# cytron-1.net
KiCad netlist of a schematic drawn in EAGLE
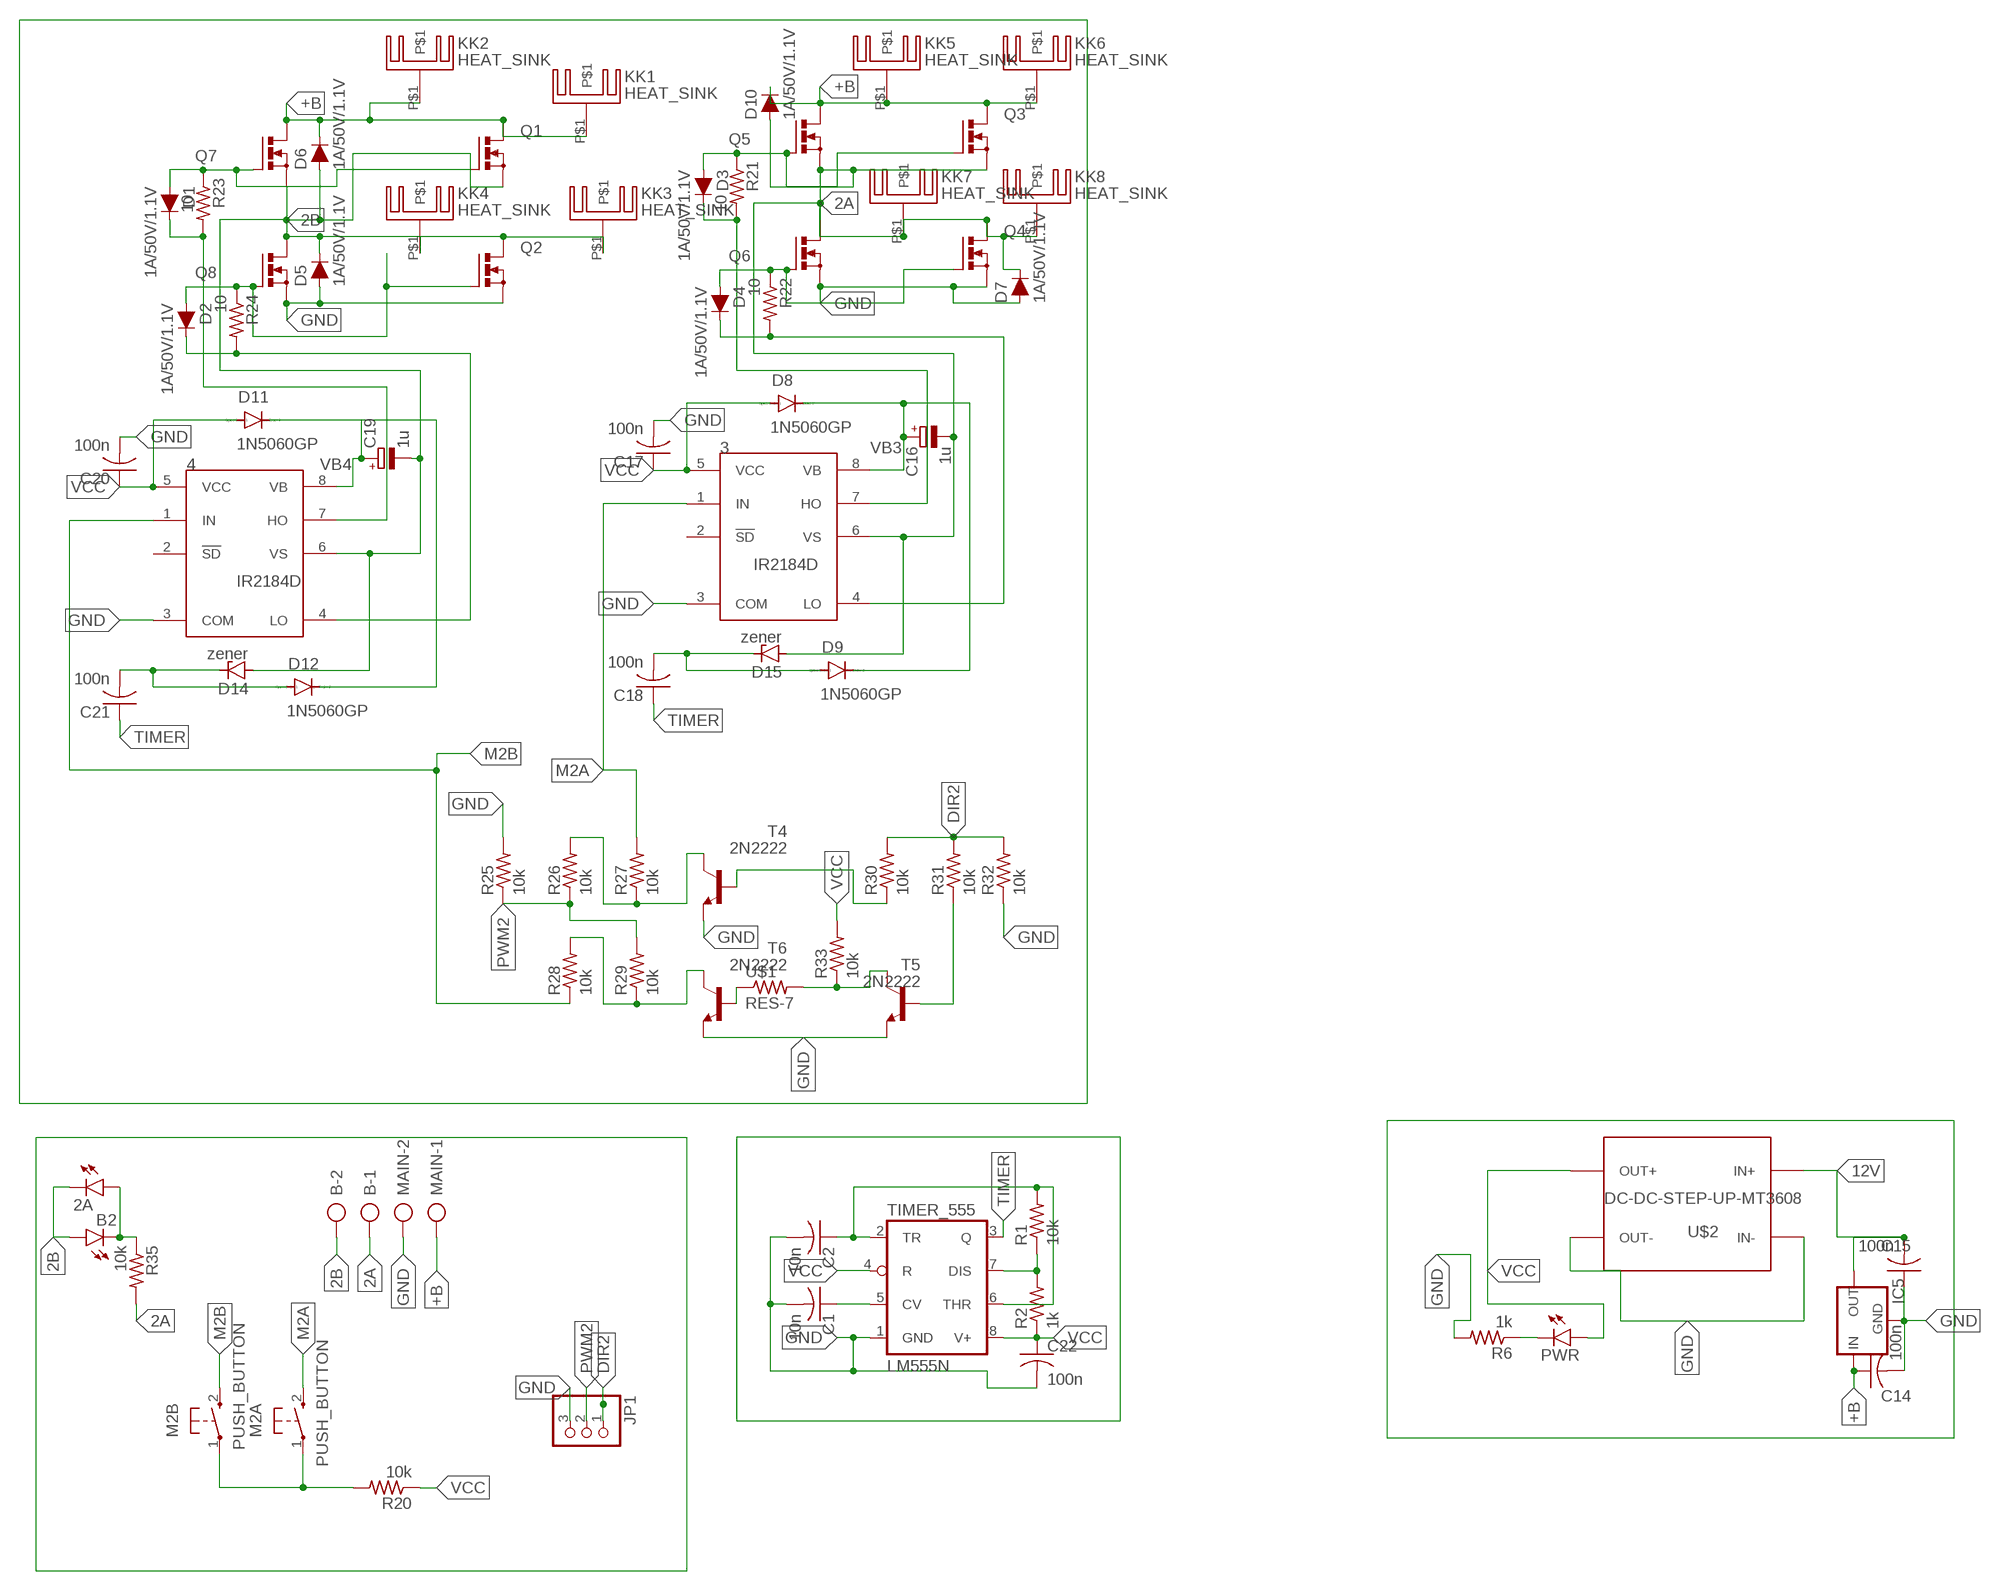
[diagram p0: schematic, sheet 1]

(export (version "E")
  (design (tool "Eeschema 10.0.6"))
  (components
    (comp (ref "2A")
      (value "LED3MM")
      (footprint "eagle-import:LED3MM")
      (libsource (lib "eagle-import") (part "LED3MM"))
    )
    (comp (ref "3")
      (value "IR2184D")
      (footprint "eagle-import:DIL08")
      (libsource (lib "eagle-import") (part "IR2184D"))
    )
    (comp (ref "4")
      (value "IR2184D")
      (footprint "eagle-import:DIL08")
      (libsource (lib "eagle-import") (part "IR2184D"))
    )
    (comp (ref "B")
      (value "ROSTA.POWER")
      (footprint "eagle-import:W239-302")
      (libsource (lib "eagle-import") (part "ROSTA.POWER"))
    )
    (comp (ref "B2")
      (value "LED3MM")
      (footprint "eagle-import:LED3MM")
      (libsource (lib "eagle-import") (part "LED3MM"))
    )
    (comp (ref "C1")
      (value "10n")
      (footprint "eagle-import:C025-025X050")
      (libsource (lib "eagle-import") (part "C-US025-025X050"))
    )
    (comp (ref "C2")
      (value "10n")
      (footprint "eagle-import:C025-025X050")
      (libsource (lib "eagle-import") (part "C-US025-025X050"))
    )
    (comp (ref "C14")
      (value "100n")
      (footprint "eagle-import:C025-025X050")
      (libsource (lib "eagle-import") (part "C-US025-025X050"))
    )
    (comp (ref "C15")
      (value "100n")
      (footprint "eagle-import:C025-025X050")
      (libsource (lib "eagle-import") (part "C-US025-025X050"))
    )
    (comp (ref "C16")
      (value "1u")
      (footprint "eagle-import:E5-5")
      (libsource (lib "eagle-import") (part "CPOL-EUE5-5"))
    )
    (comp (ref "C17")
      (value "100n")
      (footprint "eagle-import:C025-025X050")
      (libsource (lib "eagle-import") (part "C-US025-025X050"))
    )
    (comp (ref "C18")
      (value "100n")
      (footprint "eagle-import:C025-025X050")
      (libsource (lib "eagle-import") (part "C-US025-025X050"))
    )
    (comp (ref "C19")
      (value "1u")
      (footprint "eagle-import:E5-5")
      (libsource (lib "eagle-import") (part "CPOL-EUE5-5"))
    )
    (comp (ref "C20")
      (value "100n")
      (footprint "eagle-import:C025-025X050")
      (libsource (lib "eagle-import") (part "C-US025-025X050"))
    )
    (comp (ref "C21")
      (value "100n")
      (footprint "eagle-import:C025-025X050")
      (libsource (lib "eagle-import") (part "C-US025-025X050"))
    )
    (comp (ref "C22")
      (value "100n")
      (footprint "eagle-import:C025-025X050")
      (libsource (lib "eagle-import") (part "C-US025-025X050"))
    )
    (comp (ref "D1")
      (value "1A/50V/1.1V")
      (footprint "eagle-import:DIODE-1N4001")
      (libsource (lib "eagle-import") (part "DIODE(1A)-PTH"))
    )
    (comp (ref "D2")
      (value "1A/50V/1.1V")
      (footprint "eagle-import:DIODE-1N4001")
      (libsource (lib "eagle-import") (part "DIODE(1A)-PTH"))
    )
    (comp (ref "D3")
      (value "1A/50V/1.1V")
      (footprint "eagle-import:DIODE-1N4001")
      (libsource (lib "eagle-import") (part "DIODE(1A)-PTH"))
    )
    (comp (ref "D4")
      (value "1A/50V/1.1V")
      (footprint "eagle-import:DIODE-1N4001")
      (libsource (lib "eagle-import") (part "DIODE(1A)-PTH"))
    )
    (comp (ref "D5")
      (value "1A/50V/1.1V")
      (footprint "eagle-import:DIODE-1N4001")
      (libsource (lib "eagle-import") (part "DIODE(1A)-PTH"))
    )
    (comp (ref "D6")
      (value "1A/50V/1.1V")
      (footprint "eagle-import:DIODE-1N4001")
      (libsource (lib "eagle-import") (part "DIODE(1A)-PTH"))
    )
    (comp (ref "D7")
      (value "1A/50V/1.1V")
      (footprint "eagle-import:DIODE-1N4001")
      (libsource (lib "eagle-import") (part "DIODE(1A)-PTH"))
    )
    (comp (ref "D8")
      (value "1N5060GP")
      (footprint "eagle-import:DO15-12")
      (libsource (lib "eagle-import") (part "1N5060GP"))
    )
    (comp (ref "D9")
      (value "1N5060GP")
      (footprint "eagle-import:DO15-12")
      (libsource (lib "eagle-import") (part "1N5060GP"))
    )
    (comp (ref "D10")
      (value "1A/50V/1.1V")
      (footprint "eagle-import:DIODE-1N4001")
      (libsource (lib "eagle-import") (part "DIODE(1A)-PTH"))
    )
    (comp (ref "D11")
      (value "1N5060GP")
      (footprint "eagle-import:DO15-12")
      (libsource (lib "eagle-import") (part "1N5060GP"))
    )
    (comp (ref "D12")
      (value "1N5060GP")
      (footprint "eagle-import:DO15-12")
      (libsource (lib "eagle-import") (part "1N5060GP"))
    )
    (comp (ref "D14")
      (value "zener")
      (footprint "eagle-import:SOD81")
      (libsource (lib "eagle-import") (part "BZD23"))
    )
    (comp (ref "D15")
      (value "zener")
      (footprint "eagle-import:SOD81")
      (libsource (lib "eagle-import") (part "BZD23"))
    )
    (comp (ref "IC5")
      (value "78XXL")
      (footprint "eagle-import:78XXL")
      (libsource (lib "eagle-import") (part "78XXL"))
    )
    (comp (ref "JP1")
      (value "PINHD-3_DATA")
      (footprint "eagle-import:1X03_DATA")
      (libsource (lib "eagle-import") (part "PINHD-3_DATA"))
    )
    (comp (ref "KK1")
      (value "HEAT_SINK")
      (footprint "eagle-import:SK95-2M3")
      (libsource (lib "eagle-import") (part "HEAT_SINK"))
    )
    (comp (ref "KK2")
      (value "HEAT_SINK")
      (footprint "eagle-import:SK95-2M3")
      (libsource (lib "eagle-import") (part "HEAT_SINK"))
    )
    (comp (ref "KK3")
      (value "HEAT_SINK")
      (footprint "eagle-import:SK95-2M3")
      (libsource (lib "eagle-import") (part "HEAT_SINK"))
    )
    (comp (ref "KK4")
      (value "HEAT_SINK")
      (footprint "eagle-import:SK95-2M3")
      (libsource (lib "eagle-import") (part "HEAT_SINK"))
    )
    (comp (ref "KK5")
      (value "HEAT_SINK")
      (footprint "eagle-import:SK95-2M3")
      (libsource (lib "eagle-import") (part "HEAT_SINK"))
    )
    (comp (ref "KK6")
      (value "HEAT_SINK")
      (footprint "eagle-import:SK95-2M3")
      (libsource (lib "eagle-import") (part "HEAT_SINK"))
    )
    (comp (ref "KK7")
      (value "HEAT_SINK")
      (footprint "eagle-import:SK95-2M3")
      (libsource (lib "eagle-import") (part "HEAT_SINK"))
    )
    (comp (ref "KK8")
      (value "HEAT_SINK")
      (footprint "eagle-import:SK95-2M3")
      (libsource (lib "eagle-import") (part "HEAT_SINK"))
    )
    (comp (ref "M2A")
      (value "PUSH_BUTTON")
      (footprint "eagle-import:B3F-10XX")
      (libsource (lib "eagle-import") (part "PUSH_BUTTON"))
    )
    (comp (ref "M2B")
      (value "PUSH_BUTTON")
      (footprint "eagle-import:B3F-10XX")
      (libsource (lib "eagle-import") (part "PUSH_BUTTON"))
    )
    (comp (ref "MAIN")
      (value "ROSTA.POWER")
      (footprint "eagle-import:W239-302")
      (libsource (lib "eagle-import") (part "ROSTA.POWER"))
    )
    (comp (ref "PWR")
      (value "LED5MM")
      (footprint "eagle-import:LED5MM")
      (libsource (lib "eagle-import") (part "LED5MM"))
    )
    (comp (ref "Q1")
      (value "MOSFET_NTO220BV")
      (footprint "eagle-import:TO220BV")
      (libsource (lib "eagle-import") (part "MOSFET_NTO220BV"))
    )
    (comp (ref "Q2")
      (value "MOSFET_NTO220BV")
      (footprint "eagle-import:TO220BV")
      (libsource (lib "eagle-import") (part "MOSFET_NTO220BV"))
    )
    (comp (ref "Q3")
      (value "MOSFET_NTO220BV")
      (footprint "eagle-import:TO220BV")
      (libsource (lib "eagle-import") (part "MOSFET_NTO220BV"))
    )
    (comp (ref "Q4")
      (value "MOSFET_NTO220BV")
      (footprint "eagle-import:TO220BV")
      (libsource (lib "eagle-import") (part "MOSFET_NTO220BV"))
    )
    (comp (ref "Q5")
      (value "MOSFET_NTO220BV")
      (footprint "eagle-import:TO220BV")
      (libsource (lib "eagle-import") (part "MOSFET_NTO220BV"))
    )
    (comp (ref "Q6")
      (value "MOSFET_NTO220BV")
      (footprint "eagle-import:TO220BV")
      (libsource (lib "eagle-import") (part "MOSFET_NTO220BV"))
    )
    (comp (ref "Q7")
      (value "MOSFET_NTO220BV")
      (footprint "eagle-import:TO220BV")
      (libsource (lib "eagle-import") (part "MOSFET_NTO220BV"))
    )
    (comp (ref "Q8")
      (value "MOSFET_NTO220BV")
      (footprint "eagle-import:TO220BV")
      (libsource (lib "eagle-import") (part "MOSFET_NTO220BV"))
    )
    (comp (ref "R1")
      (value "10k")
      (footprint "eagle-import:0204_7")
      (libsource (lib "eagle-import") (part "R-US_0204/7"))
    )
    (comp (ref "R2")
      (value "1k")
      (footprint "eagle-import:0204_7")
      (libsource (lib "eagle-import") (part "R-US_0204/7"))
    )
    (comp (ref "R6")
      (value "1k")
      (footprint "eagle-import:0204_7")
      (libsource (lib "eagle-import") (part "R-US_0204/7"))
    )
    (comp (ref "R20")
      (value "10k")
      (footprint "eagle-import:0204_7")
      (libsource (lib "eagle-import") (part "R-US_0204/7"))
    )
    (comp (ref "R21")
      (value "10")
      (footprint "eagle-import:0204_7")
      (libsource (lib "eagle-import") (part "R-US_0204/7"))
    )
    (comp (ref "R22")
      (value "10")
      (footprint "eagle-import:0204_7")
      (libsource (lib "eagle-import") (part "R-US_0204/7"))
    )
    (comp (ref "R23")
      (value "10")
      (footprint "eagle-import:0204_7")
      (libsource (lib "eagle-import") (part "R-US_0204/7"))
    )
    (comp (ref "R24")
      (value "10")
      (footprint "eagle-import:0204_7")
      (libsource (lib "eagle-import") (part "R-US_0204/7"))
    )
    (comp (ref "R25")
      (value "10k")
      (footprint "eagle-import:0204_7")
      (libsource (lib "eagle-import") (part "R-US_0204/7"))
    )
    (comp (ref "R26")
      (value "10k")
      (footprint "eagle-import:0204_7")
      (libsource (lib "eagle-import") (part "R-US_0204/7"))
    )
    (comp (ref "R27")
      (value "10k")
      (footprint "eagle-import:0204_7")
      (libsource (lib "eagle-import") (part "R-US_0204/7"))
    )
    (comp (ref "R28")
      (value "10k")
      (footprint "eagle-import:0204_7")
      (libsource (lib "eagle-import") (part "R-US_0204/7"))
    )
    (comp (ref "R29")
      (value "10k")
      (footprint "eagle-import:0204_7")
      (libsource (lib "eagle-import") (part "R-US_0204/7"))
    )
    (comp (ref "R30")
      (value "10k")
      (footprint "eagle-import:0204_7")
      (libsource (lib "eagle-import") (part "R-US_0204/7"))
    )
    (comp (ref "R31")
      (value "10k")
      (footprint "eagle-import:0204_7")
      (libsource (lib "eagle-import") (part "R-US_0204/7"))
    )
    (comp (ref "R32")
      (value "10k")
      (footprint "eagle-import:0204_7")
      (libsource (lib "eagle-import") (part "R-US_0204/7"))
    )
    (comp (ref "R33")
      (value "10k")
      (footprint "eagle-import:0204_7")
      (libsource (lib "eagle-import") (part "R-US_0204/7"))
    )
    (comp (ref "R35")
      (value "10k")
      (footprint "eagle-import:0204_7")
      (libsource (lib "eagle-import") (part "R-US_0204/7"))
    )
    (comp (ref "T4")
      (value "2N2222")
      (footprint "eagle-import:TO18")
      (libsource (lib "eagle-import") (part "2N2222"))
    )
    (comp (ref "T5")
      (value "2N2222")
      (footprint "eagle-import:TO18")
      (libsource (lib "eagle-import") (part "2N2222"))
    )
    (comp (ref "T6")
      (value "2N2222")
      (footprint "eagle-import:TO18")
      (libsource (lib "eagle-import") (part "2N2222"))
    )
    (comp (ref "TIMER_555")
      (value "LM555N")
      (footprint "eagle-import:DIL08")
      (libsource (lib "eagle-import") (part "555NLM"))
    )
    (comp (ref "U$1")
      (value "RES-7")
      (footprint "eagle-import:0204_7")
      (libsource (lib "eagle-import") (part "RES-7"))
    )
    (comp (ref "U$2")
      (value "DC-DC-STEP-UP-MT3608")
      (footprint "eagle-import:DC-DC-STEP-UP-MT3608")
      (libsource (lib "eagle-import") (part "DC-DC-STEP-UP-MT3608"))
    )
  )
  (nets
    (net (code "1") (name "+B") (class "Default")
      (node (ref "C14") (pin "1") (pinfunction "1_1") (pintype "passive"))
      (node (ref "D10") (pin "C") (pinfunction "C_C") (pintype "passive"))
      (node (ref "D6") (pin "C") (pinfunction "C_C") (pintype "passive"))
      (node (ref "IC5") (pin "IN") (pinfunction "IN_IN") (pintype "input"))
      (node (ref "KK1") (pin "P$1") (pinfunction "P$1_P$1") (pintype "bidirectional"))
      (node (ref "KK2") (pin "P$1") (pinfunction "P$1_P$1") (pintype "bidirectional"))
      (node (ref "KK5") (pin "P$1") (pinfunction "P$1_P$1") (pintype "bidirectional"))
      (node (ref "KK6") (pin "P$1") (pinfunction "P$1_P$1") (pintype "bidirectional"))
      (node (ref "MAIN") (pin "1") (pinfunction "KL_1") (pintype "passive"))
      (node (ref "Q1") (pin "D") (pinfunction "D_D") (pintype "passive"))
      (node (ref "Q3") (pin "D") (pinfunction "D_D") (pintype "passive"))
      (node (ref "Q5") (pin "D") (pinfunction "D_D") (pintype "passive"))
      (node (ref "Q7") (pin "D") (pinfunction "D_D") (pintype "passive"))
    )
    (net (code "2") (name "/VB3") (class "Default")
      (node (ref "3") (pin "8") (pinfunction "VB_8") (pintype "power_in"))
      (node (ref "C16") (pin "+") (pinfunction "+_+") (pintype "passive"))
      (node (ref "D8") (pin "C") (pinfunction "C_C") (pintype "passive"))
      (node (ref "D9") (pin "C") (pinfunction "C_C") (pintype "passive"))
    )
    (net (code "3") (name "/VB4") (class "Default")
      (node (ref "4") (pin "8") (pinfunction "VB_8") (pintype "power_in"))
      (node (ref "C19") (pin "+") (pinfunction "+_+") (pintype "passive"))
      (node (ref "D11") (pin "C") (pinfunction "C_C") (pintype "passive"))
      (node (ref "D12") (pin "C") (pinfunction "C_C") (pintype "passive"))
    )
    (net (code "4") (name "2A") (class "Default")
      (node (ref "3") (pin "6") (pinfunction "VS_6") (pintype "power_in"))
      (node (ref "B") (pin "1") (pinfunction "KL_1") (pintype "passive"))
      (node (ref "C16") (pin "-") (pinfunction "-_-") (pintype "passive"))
      (node (ref "D10") (pin "A") (pinfunction "A_A") (pintype "passive"))
      (node (ref "D15") (pin "A") (pinfunction "A_A") (pintype "passive"))
      (node (ref "D7") (pin "C") (pinfunction "C_C") (pintype "passive"))
      (node (ref "KK7") (pin "P$1") (pinfunction "P$1_P$1") (pintype "bidirectional"))
      (node (ref "KK8") (pin "P$1") (pinfunction "P$1_P$1") (pintype "bidirectional"))
      (node (ref "Q3") (pin "S") (pinfunction "S_S") (pintype "passive"))
      (node (ref "Q4") (pin "D") (pinfunction "D_D") (pintype "passive"))
      (node (ref "Q5") (pin "S") (pinfunction "S_S") (pintype "passive"))
      (node (ref "Q6") (pin "D") (pinfunction "D_D") (pintype "passive"))
      (node (ref "R35") (pin "2") (pinfunction "2_2") (pintype "passive"))
    )
    (net (code "5") (name "2B") (class "Default")
      (node (ref "2A") (pin "K") (pinfunction "C_K") (pintype "passive"))
      (node (ref "4") (pin "6") (pinfunction "VS_6") (pintype "power_in"))
      (node (ref "B") (pin "2") (pinfunction "KL_2") (pintype "passive"))
      (node (ref "B2") (pin "A") (pinfunction "A_A") (pintype "passive"))
      (node (ref "C19") (pin "-") (pinfunction "-_-") (pintype "passive"))
      (node (ref "D14") (pin "A") (pinfunction "A_A") (pintype "passive"))
      (node (ref "D5") (pin "C") (pinfunction "C_C") (pintype "passive"))
      (node (ref "D6") (pin "A") (pinfunction "A_A") (pintype "passive"))
      (node (ref "KK3") (pin "P$1") (pinfunction "P$1_P$1") (pintype "bidirectional"))
      (node (ref "KK4") (pin "P$1") (pinfunction "P$1_P$1") (pintype "bidirectional"))
      (node (ref "Q1") (pin "S") (pinfunction "S_S") (pintype "passive"))
      (node (ref "Q2") (pin "D") (pinfunction "D_D") (pintype "passive"))
      (node (ref "Q7") (pin "S") (pinfunction "S_S") (pintype "passive"))
      (node (ref "Q8") (pin "D") (pinfunction "D_D") (pintype "passive"))
    )
    (net (code "6") (name "12V") (class "Default")
      (node (ref "C15") (pin "2") (pinfunction "2_2") (pintype "passive"))
      (node (ref "IC5") (pin "OUT") (pinfunction "OUT_OUT") (pintype "passive"))
      (node (ref "U$2") (pin "IN+") (pinfunction "IN+_IN+") (pintype "bidirectional"))
    )
    (net (code "7") (name "DIR2") (class "Default")
      (node (ref "JP1") (pin "1") (pinfunction "1_1") (pintype "passive"))
      (node (ref "R30") (pin "2") (pinfunction "2_2") (pintype "passive"))
      (node (ref "R31") (pin "2") (pinfunction "2_2") (pintype "passive"))
      (node (ref "R32") (pin "2") (pinfunction "2_2") (pintype "passive"))
    )
    (net (code "8") (name "GND") (class "Default")
      (node (ref "3") (pin "3") (pinfunction "COM_3") (pintype "power_in"))
      (node (ref "4") (pin "3") (pinfunction "COM_3") (pintype "power_in"))
      (node (ref "C1") (pin "2") (pinfunction "2_2") (pintype "passive"))
      (node (ref "C14") (pin "2") (pinfunction "2_2") (pintype "passive"))
      (node (ref "C15") (pin "1") (pinfunction "1_1") (pintype "passive"))
      (node (ref "C17") (pin "2") (pinfunction "2_2") (pintype "passive"))
      (node (ref "C2") (pin "2") (pinfunction "2_2") (pintype "passive"))
      (node (ref "C20") (pin "2") (pinfunction "2_2") (pintype "passive"))
      (node (ref "C22") (pin "2") (pinfunction "2_2") (pintype "passive"))
      (node (ref "D5") (pin "A") (pinfunction "A_A") (pintype "passive"))
      (node (ref "D7") (pin "A") (pinfunction "A_A") (pintype "passive"))
      (node (ref "IC5") (pin "GND") (pinfunction "GND_GND") (pintype "input"))
      (node (ref "JP1") (pin "3") (pinfunction "3_3") (pintype "passive"))
      (node (ref "MAIN") (pin "2") (pinfunction "KL_2") (pintype "passive"))
      (node (ref "Q2") (pin "S") (pinfunction "S_S") (pintype "passive"))
      (node (ref "Q4") (pin "S") (pinfunction "S_S") (pintype "passive"))
      (node (ref "Q6") (pin "S") (pinfunction "S_S") (pintype "passive"))
      (node (ref "Q8") (pin "S") (pinfunction "S_S") (pintype "passive"))
      (node (ref "R25") (pin "2") (pinfunction "2_2") (pintype "passive"))
      (node (ref "R32") (pin "1") (pinfunction "1_1") (pintype "passive"))
      (node (ref "R6") (pin "2") (pinfunction "2_2") (pintype "passive"))
      (node (ref "T4") (pin "1") (pinfunction "E_1") (pintype "passive"))
      (node (ref "T5") (pin "1") (pinfunction "E_1") (pintype "passive"))
      (node (ref "T6") (pin "1") (pinfunction "E_1") (pintype "passive"))
      (node (ref "TIMER_555") (pin "1") (pinfunction "GND_1") (pintype "power_in"))
      (node (ref "U$2") (pin "IN-") (pinfunction "IN-_IN-") (pintype "bidirectional"))
      (node (ref "U$2") (pin "OUT-") (pinfunction "OUT-_OUT-") (pintype "bidirectional"))
    )
    (net (code "9") (name "M2A") (class "Default")
      (node (ref "3") (pin "1") (pinfunction "IN_1") (pintype "input"))
      (node (ref "M2A") (pin "2") (pinfunction "S_2") (pintype "passive"))
      (node (ref "R27") (pin "2") (pinfunction "2_2") (pintype "passive"))
    )
    (net (code "10") (name "M2B") (class "Default")
      (node (ref "4") (pin "1") (pinfunction "IN_1") (pintype "input"))
      (node (ref "M2B") (pin "2") (pinfunction "S_2") (pintype "passive"))
      (node (ref "R28") (pin "1") (pinfunction "1_1") (pintype "passive"))
    )
    (net (code "11") (name "Net-(3-HO)") (class "Default")
      (node (ref "3") (pin "7") (pinfunction "HO_7") (pintype "output"))
      (node (ref "D3") (pin "C") (pinfunction "C_C") (pintype "passive"))
      (node (ref "R21") (pin "2") (pinfunction "2_2") (pintype "passive"))
    )
    (net (code "12") (name "Net-(3-LO)") (class "Default")
      (node (ref "3") (pin "4") (pinfunction "LO_4") (pintype "output"))
      (node (ref "D4") (pin "C") (pinfunction "C_C") (pintype "passive"))
      (node (ref "R22") (pin "2") (pinfunction "2_2") (pintype "passive"))
    )
    (net (code "13") (name "Net-(4-HO)") (class "Default")
      (node (ref "4") (pin "7") (pinfunction "HO_7") (pintype "output"))
      (node (ref "D1") (pin "C") (pinfunction "C_C") (pintype "passive"))
      (node (ref "R23") (pin "2") (pinfunction "2_2") (pintype "passive"))
    )
    (net (code "14") (name "Net-(4-LO)") (class "Default")
      (node (ref "4") (pin "4") (pinfunction "LO_4") (pintype "output"))
      (node (ref "D2") (pin "C") (pinfunction "C_C") (pintype "passive"))
      (node (ref "R24") (pin "2") (pinfunction "2_2") (pintype "passive"))
    )
    (net (code "15") (name "Net-(B2-C)") (class "Default")
      (node (ref "2A") (pin "A") (pinfunction "A_A") (pintype "passive"))
      (node (ref "B2") (pin "K") (pinfunction "C_K") (pintype "passive"))
      (node (ref "R35") (pin "1") (pinfunction "1_1") (pintype "passive"))
    )
    (net (code "16") (name "Net-(C18-Pad2)") (class "Default")
      (node (ref "C18") (pin "2") (pinfunction "2_2") (pintype "passive"))
      (node (ref "D15") (pin "C") (pinfunction "C_C") (pintype "passive"))
      (node (ref "D9") (pin "A") (pinfunction "A_A") (pintype "passive"))
    )
    (net (code "17") (name "Net-(C21-Pad2)") (class "Default")
      (node (ref "C21") (pin "2") (pinfunction "2_2") (pintype "passive"))
      (node (ref "D12") (pin "A") (pinfunction "A_A") (pintype "passive"))
      (node (ref "D14") (pin "C") (pinfunction "C_C") (pintype "passive"))
    )
    (net (code "18") (name "Net-(D1-PadA)") (class "Default")
      (node (ref "D1") (pin "A") (pinfunction "A_A") (pintype "passive"))
      (node (ref "Q1") (pin "G") (pinfunction "G_G") (pintype "passive"))
      (node (ref "Q7") (pin "G") (pinfunction "G_G") (pintype "passive"))
      (node (ref "R23") (pin "1") (pinfunction "1_1") (pintype "passive"))
    )
    (net (code "19") (name "Net-(D2-PadA)") (class "Default")
      (node (ref "D2") (pin "A") (pinfunction "A_A") (pintype "passive"))
      (node (ref "Q2") (pin "G") (pinfunction "G_G") (pintype "passive"))
      (node (ref "Q8") (pin "G") (pinfunction "G_G") (pintype "passive"))
      (node (ref "R24") (pin "1") (pinfunction "1_1") (pintype "passive"))
    )
    (net (code "20") (name "Net-(D3-PadA)") (class "Default")
      (node (ref "D3") (pin "A") (pinfunction "A_A") (pintype "passive"))
      (node (ref "Q3") (pin "G") (pinfunction "G_G") (pintype "passive"))
      (node (ref "Q5") (pin "G") (pinfunction "G_G") (pintype "passive"))
      (node (ref "R21") (pin "1") (pinfunction "1_1") (pintype "passive"))
    )
    (net (code "21") (name "Net-(D4-PadA)") (class "Default")
      (node (ref "D4") (pin "A") (pinfunction "A_A") (pintype "passive"))
      (node (ref "Q4") (pin "G") (pinfunction "G_G") (pintype "passive"))
      (node (ref "Q6") (pin "G") (pinfunction "G_G") (pintype "passive"))
      (node (ref "R22") (pin "1") (pinfunction "1_1") (pintype "passive"))
    )
    (net (code "22") (name "Net-(M2A-P)") (class "Default")
      (node (ref "M2A") (pin "1") (pinfunction "P_1") (pintype "passive"))
      (node (ref "M2B") (pin "1") (pinfunction "P_1") (pintype "passive"))
      (node (ref "R20") (pin "2") (pinfunction "2_2") (pintype "passive"))
    )
    (net (code "23") (name "Net-(PWR-C)") (class "Default")
      (node (ref "PWR") (pin "K") (pinfunction "C_K") (pintype "passive"))
      (node (ref "R6") (pin "1") (pinfunction "1_1") (pintype "passive"))
    )
    (net (code "24") (name "Net-(T4-B)") (class "Default")
      (node (ref "R30") (pin "1") (pinfunction "1_1") (pintype "passive"))
      (node (ref "T4") (pin "2") (pinfunction "B_2") (pintype "passive"))
    )
    (net (code "25") (name "Net-(T4-C)") (class "Default")
      (node (ref "R26") (pin "2") (pinfunction "2_2") (pintype "passive"))
      (node (ref "R27") (pin "1") (pinfunction "1_1") (pintype "passive"))
      (node (ref "T4") (pin "3") (pinfunction "C_3") (pintype "passive"))
    )
    (net (code "26") (name "Net-(T5-B)") (class "Default")
      (node (ref "R31") (pin "1") (pinfunction "1_1") (pintype "passive"))
      (node (ref "T5") (pin "2") (pinfunction "B_2") (pintype "passive"))
    )
    (net (code "27") (name "Net-(T5-C)") (class "Default")
      (node (ref "R33") (pin "1") (pinfunction "1_1") (pintype "passive"))
      (node (ref "T5") (pin "3") (pinfunction "C_3") (pintype "passive"))
      (node (ref "U$1") (pin "2") (pinfunction "2_2") (pintype "passive"))
    )
    (net (code "28") (name "Net-(T6-B)") (class "Default")
      (node (ref "T6") (pin "2") (pinfunction "B_2") (pintype "passive"))
      (node (ref "U$1") (pin "1") (pinfunction "1_1") (pintype "passive"))
    )
    (net (code "29") (name "Net-(T6-C)") (class "Default")
      (node (ref "R28") (pin "2") (pinfunction "2_2") (pintype "passive"))
      (node (ref "R29") (pin "1") (pinfunction "1_1") (pintype "passive"))
      (node (ref "T6") (pin "3") (pinfunction "C_3") (pintype "passive"))
    )
    (net (code "30") (name "Net-(TIMER_555-CV)") (class "Default")
      (node (ref "C1") (pin "1") (pinfunction "1_1") (pintype "passive"))
      (node (ref "TIMER_555") (pin "5") (pinfunction "CV_5") (pintype "input"))
    )
    (net (code "31") (name "Net-(TIMER_555-DIS)") (class "Default")
      (node (ref "R1") (pin "1") (pinfunction "1_1") (pintype "passive"))
      (node (ref "R2") (pin "2") (pinfunction "2_2") (pintype "passive"))
      (node (ref "TIMER_555") (pin "7") (pinfunction "DIS_7") (pintype "input"))
    )
    (net (code "32") (name "Net-(TIMER_555-THR)") (class "Default")
      (node (ref "C2") (pin "1") (pinfunction "1_1") (pintype "passive"))
      (node (ref "R1") (pin "2") (pinfunction "2_2") (pintype "passive"))
      (node (ref "TIMER_555") (pin "2") (pinfunction "TR_2") (pintype "input"))
      (node (ref "TIMER_555") (pin "6") (pinfunction "THR_6") (pintype "input"))
    )
    (net (code "33") (name "PWM2") (class "Default")
      (node (ref "JP1") (pin "2") (pinfunction "2_2") (pintype "passive"))
      (node (ref "R25") (pin "1") (pinfunction "1_1") (pintype "passive"))
      (node (ref "R26") (pin "1") (pinfunction "1_1") (pintype "passive"))
      (node (ref "R29") (pin "2") (pinfunction "2_2") (pintype "passive"))
    )
    (net (code "34") (name "TIMER") (class "Default")
      (node (ref "C18") (pin "1") (pinfunction "1_1") (pintype "passive"))
      (node (ref "C21") (pin "1") (pinfunction "1_1") (pintype "passive"))
      (node (ref "TIMER_555") (pin "3") (pinfunction "Q_3") (pintype "output"))
    )
    (net (code "35") (name "VCC") (class "Default")
      (node (ref "3") (pin "5") (pinfunction "VCC_5") (pintype "power_in"))
      (node (ref "4") (pin "5") (pinfunction "VCC_5") (pintype "power_in"))
      (node (ref "C17") (pin "1") (pinfunction "1_1") (pintype "passive"))
      (node (ref "C20") (pin "1") (pinfunction "1_1") (pintype "passive"))
      (node (ref "C22") (pin "1") (pinfunction "1_1") (pintype "passive"))
      (node (ref "D11") (pin "A") (pinfunction "A_A") (pintype "passive"))
      (node (ref "D8") (pin "A") (pinfunction "A_A") (pintype "passive"))
      (node (ref "PWR") (pin "A") (pinfunction "A_A") (pintype "passive"))
      (node (ref "R2") (pin "1") (pinfunction "1_1") (pintype "passive"))
      (node (ref "R20") (pin "1") (pinfunction "1_1") (pintype "passive"))
      (node (ref "R33") (pin "2") (pinfunction "2_2") (pintype "passive"))
      (node (ref "TIMER_555") (pin "4") (pinfunction "R_4") (pintype "input"))
      (node (ref "TIMER_555") (pin "8") (pinfunction "V+_8") (pintype "power_in"))
      (node (ref "U$2") (pin "OUT+") (pinfunction "OUT+_OUT+") (pintype "bidirectional"))
    )
    (net (code "36") (name "unconnected-(3-~{SD}-Pad2)") (class "Default")
      (node (ref "3") (pin "2") (pinfunction "~{SD}_2") (pintype "input"))
    )
    (net (code "37") (name "unconnected-(4-~{SD}-Pad2)") (class "Default")
      (node (ref "4") (pin "2") (pinfunction "~{SD}_2") (pintype "input"))
    )
  )
)
